# untitled.net
KiCad netlist of a schematic drawn in EAGLE
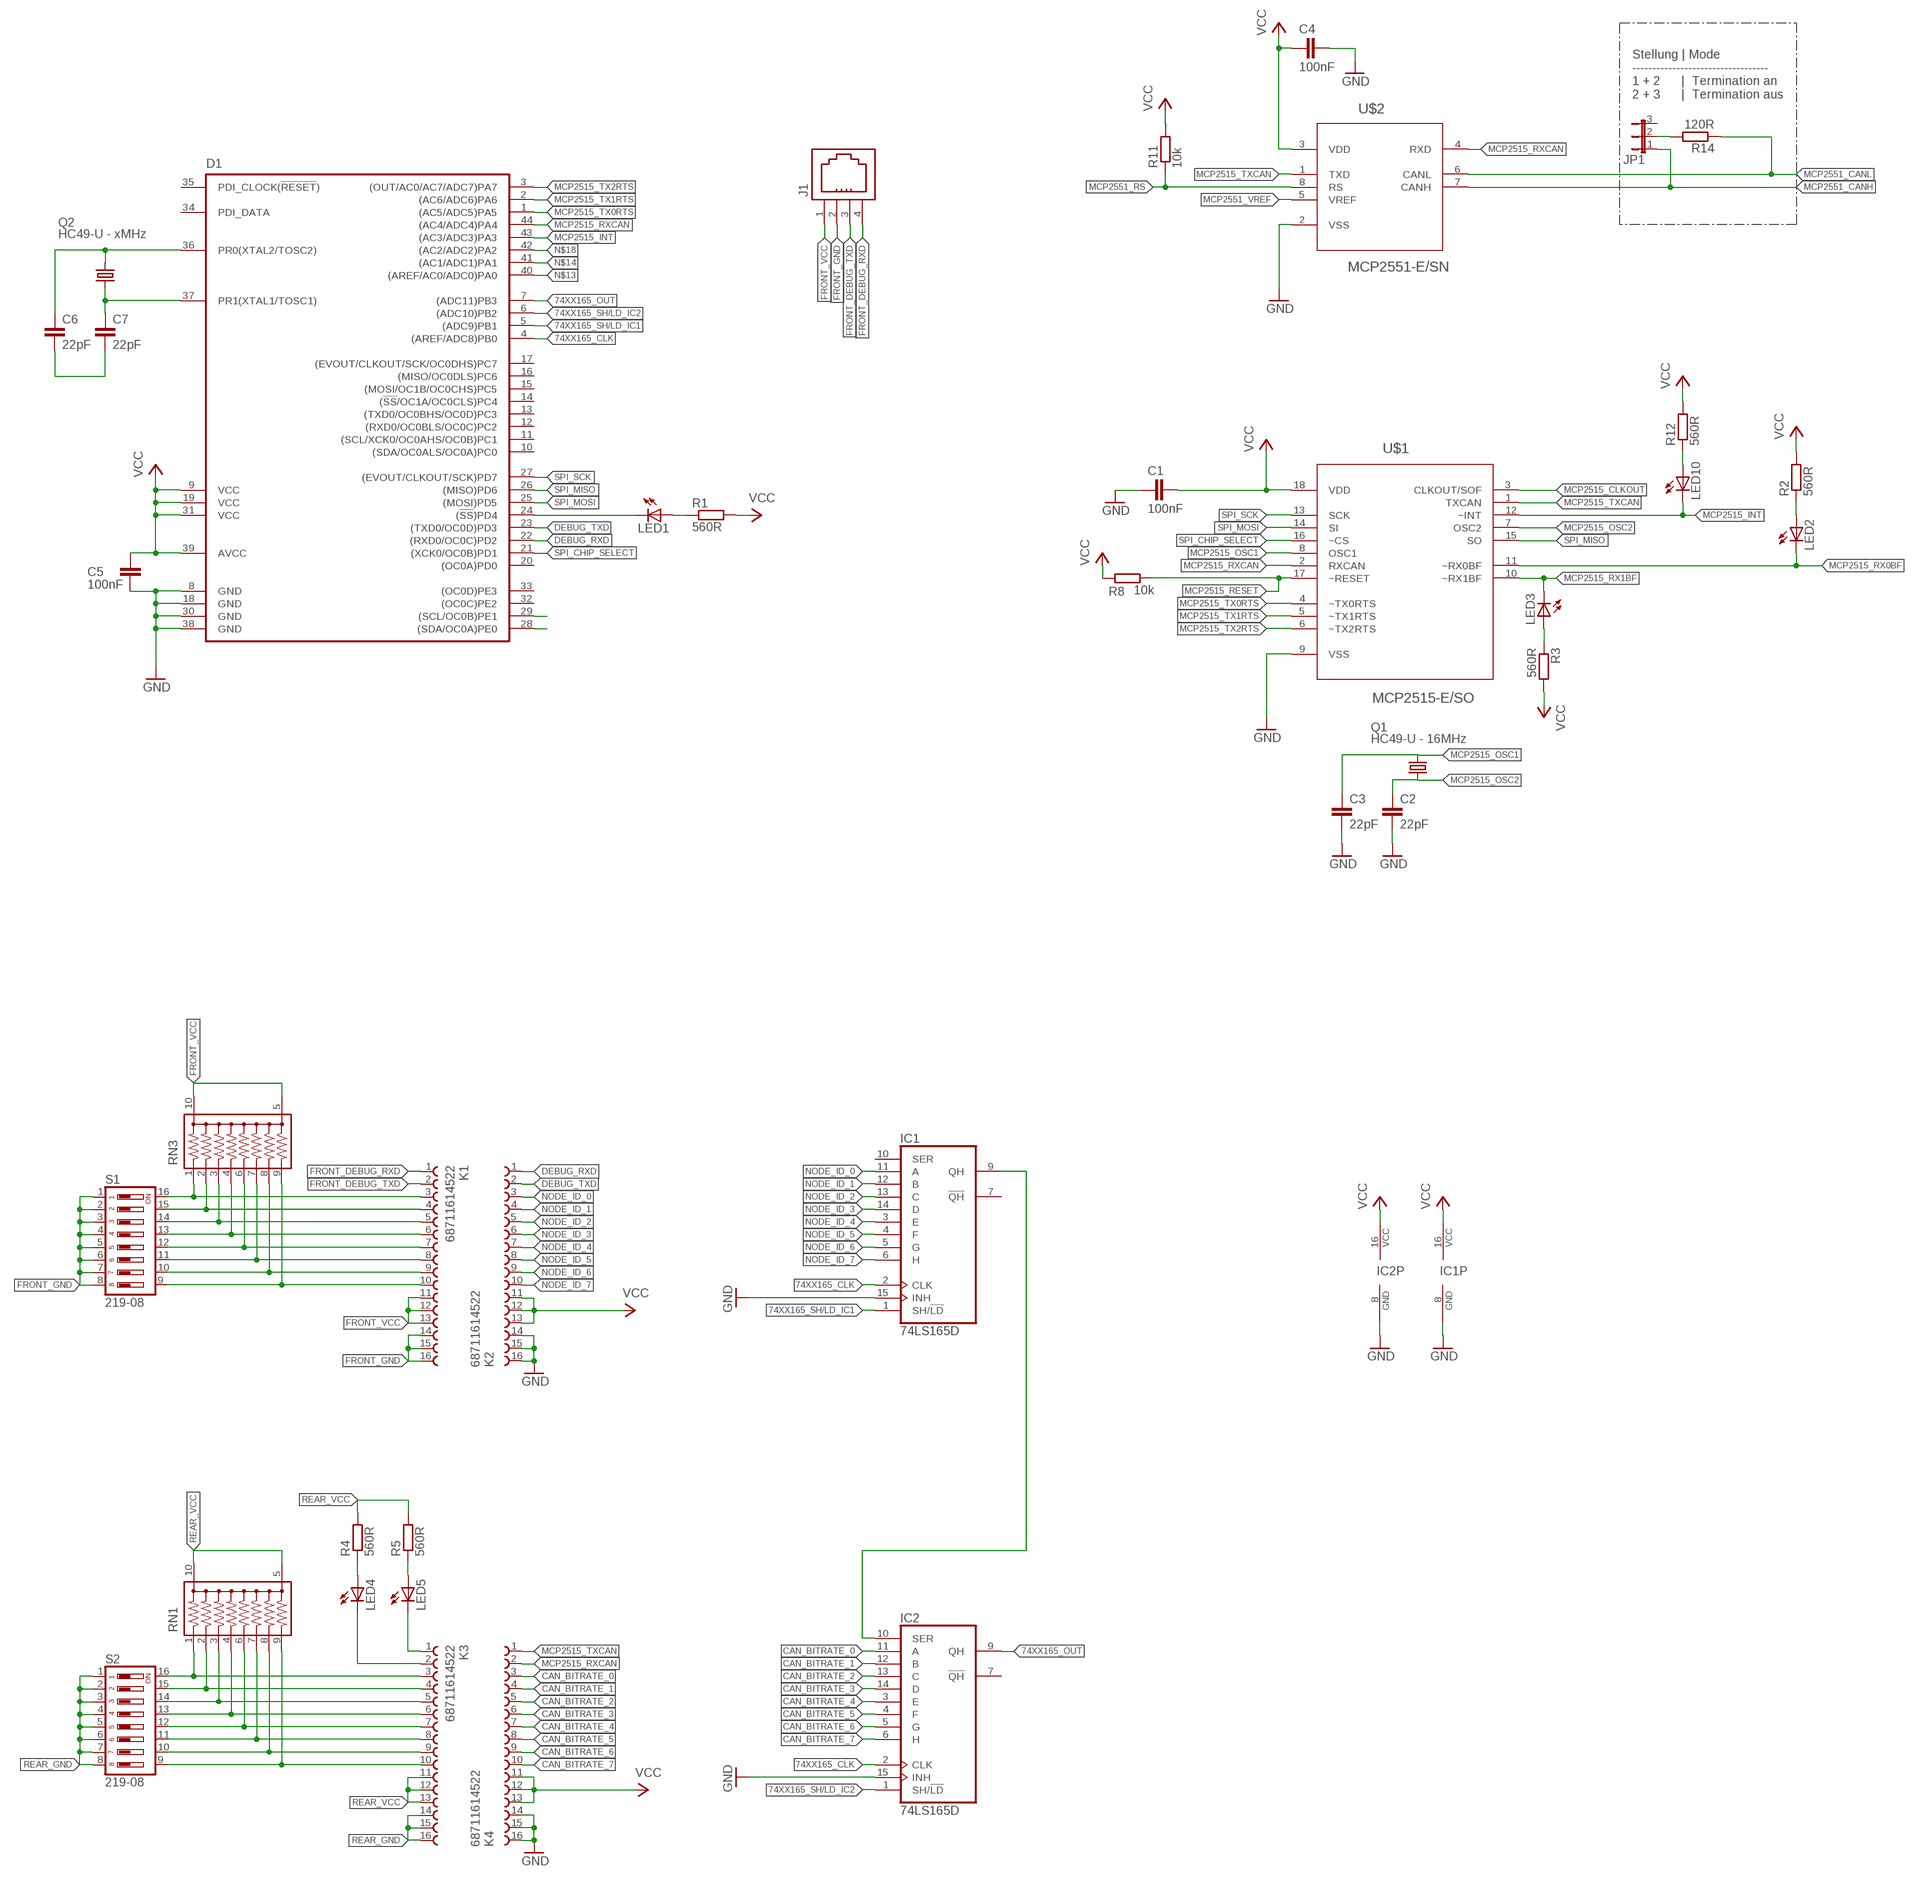
[diagram p0: schematic, sheet 1]

(export (version "E")
  (design (tool "Eeschema 10.0.6"))
  (components
    (comp (ref "C1")
      (value "100nF")
      (footprint "eagle-import:C1206")
      (libsource (lib "eagle-import") (part "C-EUC1206"))
    )
    (comp (ref "C2")
      (value "22pF")
      (footprint "eagle-import:C1206")
      (libsource (lib "eagle-import") (part "C-EUC1206"))
    )
    (comp (ref "C3")
      (value "22pF")
      (footprint "eagle-import:C1206")
      (libsource (lib "eagle-import") (part "C-EUC1206"))
    )
    (comp (ref "C4")
      (value "100nF")
      (footprint "eagle-import:C1206")
      (libsource (lib "eagle-import") (part "C-EUC1206"))
    )
    (comp (ref "C5")
      (value "100nF")
      (footprint "eagle-import:C1206")
      (libsource (lib "eagle-import") (part "C-EUC1206"))
    )
    (comp (ref "C6")
      (value "22pF")
      (footprint "eagle-import:C1206")
      (libsource (lib "eagle-import") (part "C-EUC1206"))
    )
    (comp (ref "C7")
      (value "22pF")
      (footprint "eagle-import:C1206")
      (libsource (lib "eagle-import") (part "C-EUC1206"))
    )
    (comp (ref "D1")
      (value "ATXMEGA16D4/32D4/64D4/128D4-A")
      (footprint "eagle-import:TQFP44A")
      (libsource (lib "eagle-import") (part "ATXMEGA16D4/32D4/64D4/128D4-A"))
    )
    (comp (ref "IC1")
      (value "74LS165D")
      (footprint "eagle-import:SO16")
      (libsource (lib "eagle-import") (part "74165DLS"))
    )
    (comp (ref "IC2")
      (value "74LS165D")
      (footprint "eagle-import:SO16")
      (libsource (lib "eagle-import") (part "74165DLS"))
    )
    (comp (ref "J1")
      (value "615004143821")
      (footprint "eagle-import:615004143821")
      (libsource (lib "eagle-import") (part "615004143821"))
    )
    (comp (ref "JP1")
      (value "JP2E")
      (footprint "eagle-import:JP2")
      (libsource (lib "eagle-import") (part "JP2E"))
    )
    (comp (ref "K1")
      (value "68711614522")
      (footprint "eagle-import:68711614522")
      (libsource (lib "eagle-import") (part "68711614522"))
    )
    (comp (ref "K2")
      (value "68711614522")
      (footprint "eagle-import:68711614522")
      (libsource (lib "eagle-import") (part "68711614522"))
    )
    (comp (ref "K3")
      (value "68711614522")
      (footprint "eagle-import:68711614522")
      (libsource (lib "eagle-import") (part "68711614522"))
    )
    (comp (ref "K4")
      (value "68711614522")
      (footprint "eagle-import:68711614522")
      (libsource (lib "eagle-import") (part "68711614522"))
    )
    (comp (ref "LED1")
      (value "LEDSML1206")
      (footprint "eagle-import:SML1206")
      (libsource (lib "eagle-import") (part "LEDSML1206"))
    )
    (comp (ref "LED2")
      (value "LEDSML1206")
      (footprint "eagle-import:SML1206")
      (libsource (lib "eagle-import") (part "LEDSML1206"))
    )
    (comp (ref "LED3")
      (value "LEDSML1206")
      (footprint "eagle-import:SML1206")
      (libsource (lib "eagle-import") (part "LEDSML1206"))
    )
    (comp (ref "LED4")
      (value "LEDSML1206")
      (footprint "eagle-import:SML1206")
      (libsource (lib "eagle-import") (part "LEDSML1206"))
    )
    (comp (ref "LED5")
      (value "LEDSML1206")
      (footprint "eagle-import:SML1206")
      (libsource (lib "eagle-import") (part "LEDSML1206"))
    )
    (comp (ref "LED10")
      (value "LEDSML1206")
      (footprint "eagle-import:SML1206")
      (libsource (lib "eagle-import") (part "LEDSML1206"))
    )
    (comp (ref "Q1")
      (value "HC49-U - 16MHz")
      (footprint "eagle-import:HC49")
      (libsource (lib "eagle-import") (part "HC49-U"))
    )
    (comp (ref "Q2")
      (value "HC49-U - xMHz")
      (footprint "eagle-import:HC49")
      (libsource (lib "eagle-import") (part "HC49-U"))
    )
    (comp (ref "R1")
      (value "560R")
      (footprint "eagle-import:R1206")
      (libsource (lib "eagle-import") (part "R-EU_R1206"))
    )
    (comp (ref "R2")
      (value "560R")
      (footprint "eagle-import:R1206")
      (libsource (lib "eagle-import") (part "R-EU_R1206"))
    )
    (comp (ref "R3")
      (value "560R")
      (footprint "eagle-import:R1206")
      (libsource (lib "eagle-import") (part "R-EU_R1206"))
    )
    (comp (ref "R4")
      (value "560R")
      (footprint "eagle-import:R1206")
      (libsource (lib "eagle-import") (part "R-EU_R1206"))
    )
    (comp (ref "R5")
      (value "560R")
      (footprint "eagle-import:R1206")
      (libsource (lib "eagle-import") (part "R-EU_R1206"))
    )
    (comp (ref "R8")
      (value "10k")
      (footprint "eagle-import:R1206")
      (libsource (lib "eagle-import") (part "R-EU_R1206"))
    )
    (comp (ref "R11")
      (value "10k")
      (footprint "eagle-import:R1206")
      (libsource (lib "eagle-import") (part "R-EU_R1206"))
    )
    (comp (ref "R12")
      (value "560R")
      (footprint "eagle-import:R1206")
      (libsource (lib "eagle-import") (part "R-EU_R1206"))
    )
    (comp (ref "R14")
      (value "120R")
      (footprint "eagle-import:R1206")
      (libsource (lib "eagle-import") (part "R-EU_R1206"))
    )
    (comp (ref "RN1")
      (value "745-10")
      (footprint "eagle-import:745-10")
      (libsource (lib "eagle-import") (part "745-10"))
    )
    (comp (ref "RN3")
      (value "745-10")
      (footprint "eagle-import:745-10")
      (libsource (lib "eagle-import") (part "745-10"))
    )
    (comp (ref "S1")
      (value "219-08")
      (footprint "eagle-import:CTS-219-08")
      (libsource (lib "eagle-import") (part "219-08"))
    )
    (comp (ref "S2")
      (value "219-08")
      (footprint "eagle-import:CTS-219-08")
      (libsource (lib "eagle-import") (part "219-08"))
    )
    (comp (ref "U$1")
      (value "MCP2515-E/SO")
      (footprint "eagle-import:SOIC127P1030X265-18N")
      (libsource (lib "eagle-import") (part "MCP2515-E/SO"))
    )
    (comp (ref "U$2")
      (value "MCP2551-E/SN")
      (footprint "eagle-import:SOIC127P600X175-8N")
      (libsource (lib "eagle-import") (part "MCP2551-E/SN"))
    )
  )
  (nets
    (net (code "1") (name "74XX165_CLK") (class "Default")
      (node (ref "D1") (pin "4") (pinfunction "(AREF/ADC8)PB0_4") (pintype "bidirectional"))
      (node (ref "IC1") (pin "2") (pinfunction "CLK_2") (pintype "input"))
      (node (ref "IC2") (pin "2") (pinfunction "CLK_2") (pintype "input"))
    )
    (net (code "2") (name "74XX165_OUT") (class "Default")
      (node (ref "D1") (pin "7") (pinfunction "(ADC11)PB3_7") (pintype "bidirectional"))
      (node (ref "IC2") (pin "9") (pinfunction "QH_9") (pintype "output"))
    )
    (net (code "3") (name "74XX165_SH{slash}LD_IC1") (class "Default")
      (node (ref "D1") (pin "5") (pinfunction "(ADC9)PB1_5") (pintype "bidirectional"))
      (node (ref "IC1") (pin "1") (pinfunction "SH/~{LD}_1") (pintype "input"))
    )
    (net (code "4") (name "74XX165_SH{slash}LD_IC2") (class "Default")
      (node (ref "D1") (pin "6") (pinfunction "(ADC10)PB2_6") (pintype "bidirectional"))
      (node (ref "IC2") (pin "1") (pinfunction "SH/~{LD}_1") (pintype "input"))
    )
    (net (code "5") (name "CAN_BITRATE_0") (class "Default")
      (node (ref "IC2") (pin "11") (pinfunction "A_11") (pintype "input"))
      (node (ref "K4") (pin "3") (pinfunction "3_3") (pintype "passive"))
    )
    (net (code "6") (name "CAN_BITRATE_1") (class "Default")
      (node (ref "IC2") (pin "12") (pinfunction "B_12") (pintype "input"))
      (node (ref "K4") (pin "4") (pinfunction "4_4") (pintype "passive"))
    )
    (net (code "7") (name "CAN_BITRATE_2") (class "Default")
      (node (ref "IC2") (pin "13") (pinfunction "C_13") (pintype "input"))
      (node (ref "K4") (pin "5") (pinfunction "5_5") (pintype "passive"))
    )
    (net (code "8") (name "CAN_BITRATE_3") (class "Default")
      (node (ref "IC2") (pin "14") (pinfunction "D_14") (pintype "input"))
      (node (ref "K4") (pin "6") (pinfunction "6_6") (pintype "passive"))
    )
    (net (code "9") (name "CAN_BITRATE_4") (class "Default")
      (node (ref "IC2") (pin "3") (pinfunction "E_3") (pintype "input"))
      (node (ref "K4") (pin "7") (pinfunction "7_7") (pintype "passive"))
    )
    (net (code "10") (name "CAN_BITRATE_5") (class "Default")
      (node (ref "IC2") (pin "4") (pinfunction "F_4") (pintype "input"))
      (node (ref "K4") (pin "8") (pinfunction "8_8") (pintype "passive"))
    )
    (net (code "11") (name "CAN_BITRATE_6") (class "Default")
      (node (ref "IC2") (pin "5") (pinfunction "G_5") (pintype "input"))
      (node (ref "K4") (pin "9") (pinfunction "9_9") (pintype "passive"))
    )
    (net (code "12") (name "CAN_BITRATE_7") (class "Default")
      (node (ref "IC2") (pin "6") (pinfunction "H_6") (pintype "input"))
      (node (ref "K4") (pin "10") (pinfunction "10_10") (pintype "passive"))
    )
    (net (code "13") (name "DEBUG_RXD") (class "Default")
      (node (ref "D1") (pin "22") (pinfunction "(RXD0/OC0C)PD2_22") (pintype "bidirectional"))
      (node (ref "K2") (pin "1") (pinfunction "1_1") (pintype "passive"))
    )
    (net (code "14") (name "DEBUG_TXD") (class "Default")
      (node (ref "D1") (pin "23") (pinfunction "(TXD0/OC0D)PD3_23") (pintype "bidirectional"))
      (node (ref "K2") (pin "2") (pinfunction "2_2") (pintype "passive"))
    )
    (net (code "15") (name "FRONT_DEBUG_RXD") (class "Default")
      (node (ref "J1") (pin "4") (pinfunction "1_4") (pintype "passive"))
      (node (ref "K1") (pin "1") (pinfunction "1_1") (pintype "passive"))
    )
    (net (code "16") (name "FRONT_DEBUG_TXD") (class "Default")
      (node (ref "J1") (pin "3") (pinfunction "2_3") (pintype "passive"))
      (node (ref "K1") (pin "2") (pinfunction "2_2") (pintype "passive"))
    )
    (net (code "17") (name "FRONT_GND") (class "Default")
      (node (ref "J1") (pin "2") (pinfunction "3_2") (pintype "passive"))
      (node (ref "K1") (pin "14") (pinfunction "14_14") (pintype "passive"))
      (node (ref "K1") (pin "15") (pinfunction "15_15") (pintype "passive"))
      (node (ref "K1") (pin "16") (pinfunction "16_16") (pintype "passive"))
      (node (ref "S1") (pin "1") (pinfunction "1_1") (pintype "passive"))
      (node (ref "S1") (pin "2") (pinfunction "2_2") (pintype "passive"))
      (node (ref "S1") (pin "3") (pinfunction "3_3") (pintype "passive"))
      (node (ref "S1") (pin "4") (pinfunction "4_4") (pintype "passive"))
      (node (ref "S1") (pin "5") (pinfunction "5_5") (pintype "passive"))
      (node (ref "S1") (pin "6") (pinfunction "6_6") (pintype "passive"))
      (node (ref "S1") (pin "7") (pinfunction "7_7") (pintype "passive"))
      (node (ref "S1") (pin "8") (pinfunction "8_8") (pintype "passive"))
    )
    (net (code "18") (name "FRONT_VCC") (class "Default")
      (node (ref "J1") (pin "1") (pinfunction "4_1") (pintype "passive"))
      (node (ref "K1") (pin "11") (pinfunction "11_11") (pintype "passive"))
      (node (ref "K1") (pin "12") (pinfunction "12_12") (pintype "passive"))
      (node (ref "K1") (pin "13") (pinfunction "13_13") (pintype "passive"))
      (node (ref "RN3") (pin "10") (pinfunction "10_10") (pintype "passive"))
      (node (ref "RN3") (pin "5") (pinfunction "5_5") (pintype "passive"))
    )
    (net (code "19") (name "GND") (class "Default")
      (node (ref "C1") (pin "2") (pinfunction "2_2") (pintype "passive"))
      (node (ref "C2") (pin "2") (pinfunction "2_2") (pintype "passive"))
      (node (ref "C3") (pin "2") (pinfunction "2_2") (pintype "passive"))
      (node (ref "C4") (pin "1") (pinfunction "1_1") (pintype "passive"))
      (node (ref "C5") (pin "2") (pinfunction "2_2") (pintype "passive"))
      (node (ref "D1") (pin "18") (pinfunction "GND_18") (pintype "power_in"))
      (node (ref "D1") (pin "30") (pinfunction "GND_30") (pintype "power_in"))
      (node (ref "D1") (pin "38") (pinfunction "GND_38") (pintype "power_in"))
      (node (ref "D1") (pin "8") (pinfunction "GND_8") (pintype "power_in"))
      (node (ref "IC1") (pin "15") (pinfunction "INH_15") (pintype "input"))
      (node (ref "IC1") (pin "8") (pinfunction "GND_8") (pintype "power_in"))
      (node (ref "IC2") (pin "15") (pinfunction "INH_15") (pintype "input"))
      (node (ref "IC2") (pin "8") (pinfunction "GND_8") (pintype "power_in"))
      (node (ref "K2") (pin "14") (pinfunction "14_14") (pintype "passive"))
      (node (ref "K2") (pin "15") (pinfunction "15_15") (pintype "passive"))
      (node (ref "K2") (pin "16") (pinfunction "16_16") (pintype "passive"))
      (node (ref "K4") (pin "14") (pinfunction "14_14") (pintype "passive"))
      (node (ref "K4") (pin "15") (pinfunction "15_15") (pintype "passive"))
      (node (ref "K4") (pin "16") (pinfunction "16_16") (pintype "passive"))
      (node (ref "U$1") (pin "9") (pinfunction "VSS_9") (pintype "power_in"))
      (node (ref "U$2") (pin "2") (pinfunction "VSS_2") (pintype "power_in"))
    )
    (net (code "20") (name "MCP2515_CLKOUT") (class "Default")
      (node (ref "U$1") (pin "3") (pinfunction "CLKOUT/SOF_3") (pintype "output"))
    )
    (net (code "21") (name "MCP2515_INT") (class "Default")
      (node (ref "D1") (pin "43") (pinfunction "(AC3/ADC3)PA3_43") (pintype "bidirectional"))
      (node (ref "LED10") (pin "C") (pinfunction "C_C") (pintype "passive"))
      (node (ref "U$1") (pin "12") (pinfunction "~{INT}_12") (pintype "output"))
    )
    (net (code "22") (name "MCP2515_OSC1") (class "Default")
      (node (ref "C3") (pin "1") (pinfunction "1_1") (pintype "passive"))
      (node (ref "Q1") (pin "2") (pinfunction "2_2") (pintype "passive"))
      (node (ref "U$1") (pin "8") (pinfunction "OSC1_8") (pintype "input"))
    )
    (net (code "23") (name "MCP2515_OSC2") (class "Default")
      (node (ref "C2") (pin "1") (pinfunction "1_1") (pintype "passive"))
      (node (ref "Q1") (pin "1") (pinfunction "1_1") (pintype "passive"))
      (node (ref "U$1") (pin "7") (pinfunction "OSC2_7") (pintype "output"))
    )
    (net (code "24") (name "MCP2515_RESET") (class "Default")
      (node (ref "R8") (pin "1") (pinfunction "1_1") (pintype "passive"))
      (node (ref "U$1") (pin "17") (pinfunction "~{RESET}_17") (pintype "input"))
    )
    (net (code "25") (name "MCP2515_RX0BF") (class "Default")
      (node (ref "LED2") (pin "C") (pinfunction "C_C") (pintype "passive"))
      (node (ref "U$1") (pin "11") (pinfunction "~{RX0BF}_11") (pintype "output"))
    )
    (net (code "26") (name "MCP2515_RX1BF") (class "Default")
      (node (ref "LED3") (pin "C") (pinfunction "C_C") (pintype "passive"))
      (node (ref "U$1") (pin "10") (pinfunction "~{RX1BF}_10") (pintype "output"))
    )
    (net (code "27") (name "MCP2515_RXCAN") (class "Default")
      (node (ref "D1") (pin "44") (pinfunction "(AC4/ADC4)PA4_44") (pintype "bidirectional"))
      (node (ref "K4") (pin "2") (pinfunction "2_2") (pintype "passive"))
      (node (ref "U$1") (pin "2") (pinfunction "RXCAN_2") (pintype "input"))
      (node (ref "U$2") (pin "4") (pinfunction "RXD_4") (pintype "output"))
    )
    (net (code "28") (name "MCP2515_TX0RTS") (class "Default")
      (node (ref "D1") (pin "1") (pinfunction "(AC5/ADC5)PA5_1") (pintype "bidirectional"))
      (node (ref "U$1") (pin "4") (pinfunction "~{TX0RTS}_4") (pintype "input"))
    )
    (net (code "29") (name "MCP2515_TX1RTS") (class "Default")
      (node (ref "D1") (pin "2") (pinfunction "(AC6/ADC6)PA6_2") (pintype "bidirectional"))
      (node (ref "U$1") (pin "5") (pinfunction "~{TX1RTS}_5") (pintype "input"))
    )
    (net (code "30") (name "MCP2515_TX2RTS") (class "Default")
      (node (ref "D1") (pin "3") (pinfunction "(OUT/AC0/AC7/ADC7)PA7_3") (pintype "bidirectional"))
      (node (ref "U$1") (pin "6") (pinfunction "~{TX2RTS}_6") (pintype "input"))
    )
    (net (code "31") (name "MCP2515_TXCAN") (class "Default")
      (node (ref "K4") (pin "1") (pinfunction "1_1") (pintype "passive"))
      (node (ref "U$1") (pin "1") (pinfunction "TXCAN_1") (pintype "output"))
      (node (ref "U$2") (pin "1") (pinfunction "TXD_1") (pintype "input"))
    )
    (net (code "32") (name "MCP2551_CANH") (class "Default")
      (node (ref "JP1") (pin "1") (pinfunction "1_1") (pintype "passive"))
      (node (ref "U$2") (pin "7") (pinfunction "CANH_7") (pintype "output"))
    )
    (net (code "33") (name "MCP2551_CANL") (class "Default")
      (node (ref "R14") (pin "1") (pinfunction "1_1") (pintype "passive"))
      (node (ref "U$2") (pin "6") (pinfunction "CANL_6") (pintype "output"))
    )
    (net (code "34") (name "MCP2551_RS") (class "Default")
      (node (ref "R11") (pin "1") (pinfunction "1_1") (pintype "passive"))
      (node (ref "U$2") (pin "8") (pinfunction "RS_8") (pintype "input"))
    )
    (net (code "35") (name "MCP2551_VREF") (class "Default")
      (node (ref "U$2") (pin "5") (pinfunction "VREF_5") (pintype "input"))
    )
    (net (code "36") (name "N$13") (class "Default")
      (node (ref "D1") (pin "40") (pinfunction "(AREF/AC0/ADC0)PA0_40") (pintype "bidirectional"))
    )
    (net (code "37") (name "N$14") (class "Default")
      (node (ref "D1") (pin "41") (pinfunction "(AC1/ADC1)PA1_41") (pintype "bidirectional"))
    )
    (net (code "38") (name "N$18") (class "Default")
      (node (ref "D1") (pin "42") (pinfunction "(AC2/ADC2)PA2_42") (pintype "bidirectional"))
    )
    (net (code "39") (name "NODE_ID_0") (class "Default")
      (node (ref "IC1") (pin "11") (pinfunction "A_11") (pintype "input"))
      (node (ref "K2") (pin "3") (pinfunction "3_3") (pintype "passive"))
    )
    (net (code "40") (name "NODE_ID_1") (class "Default")
      (node (ref "IC1") (pin "12") (pinfunction "B_12") (pintype "input"))
      (node (ref "K2") (pin "4") (pinfunction "4_4") (pintype "passive"))
    )
    (net (code "41") (name "NODE_ID_2") (class "Default")
      (node (ref "IC1") (pin "13") (pinfunction "C_13") (pintype "input"))
      (node (ref "K2") (pin "5") (pinfunction "5_5") (pintype "passive"))
    )
    (net (code "42") (name "NODE_ID_3") (class "Default")
      (node (ref "IC1") (pin "14") (pinfunction "D_14") (pintype "input"))
      (node (ref "K2") (pin "6") (pinfunction "6_6") (pintype "passive"))
    )
    (net (code "43") (name "NODE_ID_4") (class "Default")
      (node (ref "IC1") (pin "3") (pinfunction "E_3") (pintype "input"))
      (node (ref "K2") (pin "7") (pinfunction "7_7") (pintype "passive"))
    )
    (net (code "44") (name "NODE_ID_5") (class "Default")
      (node (ref "IC1") (pin "4") (pinfunction "F_4") (pintype "input"))
      (node (ref "K2") (pin "8") (pinfunction "8_8") (pintype "passive"))
    )
    (net (code "45") (name "NODE_ID_6") (class "Default")
      (node (ref "IC1") (pin "5") (pinfunction "G_5") (pintype "input"))
      (node (ref "K2") (pin "9") (pinfunction "9_9") (pintype "passive"))
    )
    (net (code "46") (name "NODE_ID_7") (class "Default")
      (node (ref "IC1") (pin "6") (pinfunction "H_6") (pintype "input"))
      (node (ref "K2") (pin "10") (pinfunction "10_10") (pintype "passive"))
    )
    (net (code "47") (name "Net-(C6-Pad2)") (class "Default")
      (node (ref "C6") (pin "2") (pinfunction "2_2") (pintype "passive"))
      (node (ref "C7") (pin "2") (pinfunction "2_2") (pintype "passive"))
    )
    (net (code "48") (name "Net-(D1-(~{SS})PD4)") (class "Default")
      (node (ref "D1") (pin "24") (pinfunction "(~{SS})PD4_24") (pintype "bidirectional"))
      (node (ref "LED1") (pin "C") (pinfunction "C_C") (pintype "passive"))
    )
    (net (code "49") (name "Net-(D1-PR0(XTAL2{slash}TOSC2))") (class "Default")
      (node (ref "C6") (pin "1") (pinfunction "1_1") (pintype "passive"))
      (node (ref "D1") (pin "36") (pinfunction "PR0(XTAL2/TOSC2)_36") (pintype "bidirectional"))
      (node (ref "Q2") (pin "2") (pinfunction "2_2") (pintype "passive"))
    )
    (net (code "50") (name "Net-(D1-PR1(XTAL1{slash}TOSC1))") (class "Default")
      (node (ref "C7") (pin "1") (pinfunction "1_1") (pintype "passive"))
      (node (ref "D1") (pin "37") (pinfunction "PR1(XTAL1/TOSC1)_37") (pintype "bidirectional"))
      (node (ref "Q2") (pin "1") (pinfunction "1_1") (pintype "passive"))
    )
    (net (code "51") (name "Net-(IC1A-QH)") (class "Default")
      (node (ref "IC1") (pin "9") (pinfunction "QH_9") (pintype "output"))
      (node (ref "IC2") (pin "10") (pinfunction "SER_10") (pintype "input"))
    )
    (net (code "52") (name "Net-(JP1-Pad2)") (class "Default")
      (node (ref "JP1") (pin "2") (pinfunction "2_2") (pintype "passive"))
      (node (ref "R14") (pin "2") (pinfunction "2_2") (pintype "passive"))
    )
    (net (code "53") (name "Net-(K1-Pad3)") (class "Default")
      (node (ref "K1") (pin "3") (pinfunction "3_3") (pintype "passive"))
      (node (ref "RN3") (pin "1") (pinfunction "1_1") (pintype "passive"))
      (node (ref "S1") (pin "16") (pinfunction "16_16") (pintype "passive"))
    )
    (net (code "54") (name "Net-(K1-Pad4)") (class "Default")
      (node (ref "K1") (pin "4") (pinfunction "4_4") (pintype "passive"))
      (node (ref "RN3") (pin "2") (pinfunction "2_2") (pintype "passive"))
      (node (ref "S1") (pin "15") (pinfunction "15_15") (pintype "passive"))
    )
    (net (code "55") (name "Net-(K1-Pad5)") (class "Default")
      (node (ref "K1") (pin "5") (pinfunction "5_5") (pintype "passive"))
      (node (ref "RN3") (pin "3") (pinfunction "3_3") (pintype "passive"))
      (node (ref "S1") (pin "14") (pinfunction "14_14") (pintype "passive"))
    )
    (net (code "56") (name "Net-(K1-Pad6)") (class "Default")
      (node (ref "K1") (pin "6") (pinfunction "6_6") (pintype "passive"))
      (node (ref "RN3") (pin "4") (pinfunction "4_4") (pintype "passive"))
      (node (ref "S1") (pin "13") (pinfunction "13_13") (pintype "passive"))
    )
    (net (code "57") (name "Net-(K1-Pad7)") (class "Default")
      (node (ref "K1") (pin "7") (pinfunction "7_7") (pintype "passive"))
      (node (ref "RN3") (pin "6") (pinfunction "6_6") (pintype "passive"))
      (node (ref "S1") (pin "12") (pinfunction "12_12") (pintype "passive"))
    )
    (net (code "58") (name "Net-(K1-Pad8)") (class "Default")
      (node (ref "K1") (pin "8") (pinfunction "8_8") (pintype "passive"))
      (node (ref "RN3") (pin "7") (pinfunction "7_7") (pintype "passive"))
      (node (ref "S1") (pin "11") (pinfunction "11_11") (pintype "passive"))
    )
    (net (code "59") (name "Net-(K1-Pad9)") (class "Default")
      (node (ref "K1") (pin "9") (pinfunction "9_9") (pintype "passive"))
      (node (ref "RN3") (pin "8") (pinfunction "8_8") (pintype "passive"))
      (node (ref "S1") (pin "10") (pinfunction "10_10") (pintype "passive"))
    )
    (net (code "60") (name "Net-(K1-Pad10)") (class "Default")
      (node (ref "K1") (pin "10") (pinfunction "10_10") (pintype "passive"))
      (node (ref "RN3") (pin "9") (pinfunction "9_9") (pintype "passive"))
      (node (ref "S1") (pin "9") (pinfunction "9_9") (pintype "passive"))
    )
    (net (code "61") (name "Net-(K3-Pad1)") (class "Default")
      (node (ref "K3") (pin "1") (pinfunction "1_1") (pintype "passive"))
      (node (ref "LED5") (pin "C") (pinfunction "C_C") (pintype "passive"))
    )
    (net (code "62") (name "Net-(K3-Pad2)") (class "Default")
      (node (ref "K3") (pin "2") (pinfunction "2_2") (pintype "passive"))
      (node (ref "LED4") (pin "C") (pinfunction "C_C") (pintype "passive"))
    )
    (net (code "63") (name "Net-(K3-Pad3)") (class "Default")
      (node (ref "K3") (pin "3") (pinfunction "3_3") (pintype "passive"))
      (node (ref "RN1") (pin "1") (pinfunction "1_1") (pintype "passive"))
      (node (ref "S2") (pin "16") (pinfunction "16_16") (pintype "passive"))
    )
    (net (code "64") (name "Net-(K3-Pad4)") (class "Default")
      (node (ref "K3") (pin "4") (pinfunction "4_4") (pintype "passive"))
      (node (ref "RN1") (pin "2") (pinfunction "2_2") (pintype "passive"))
      (node (ref "S2") (pin "15") (pinfunction "15_15") (pintype "passive"))
    )
    (net (code "65") (name "Net-(K3-Pad5)") (class "Default")
      (node (ref "K3") (pin "5") (pinfunction "5_5") (pintype "passive"))
      (node (ref "RN1") (pin "3") (pinfunction "3_3") (pintype "passive"))
      (node (ref "S2") (pin "14") (pinfunction "14_14") (pintype "passive"))
    )
    (net (code "66") (name "Net-(K3-Pad6)") (class "Default")
      (node (ref "K3") (pin "6") (pinfunction "6_6") (pintype "passive"))
      (node (ref "RN1") (pin "4") (pinfunction "4_4") (pintype "passive"))
      (node (ref "S2") (pin "13") (pinfunction "13_13") (pintype "passive"))
    )
    (net (code "67") (name "Net-(K3-Pad7)") (class "Default")
      (node (ref "K3") (pin "7") (pinfunction "7_7") (pintype "passive"))
      (node (ref "RN1") (pin "6") (pinfunction "6_6") (pintype "passive"))
      (node (ref "S2") (pin "12") (pinfunction "12_12") (pintype "passive"))
    )
    (net (code "68") (name "Net-(K3-Pad8)") (class "Default")
      (node (ref "K3") (pin "8") (pinfunction "8_8") (pintype "passive"))
      (node (ref "RN1") (pin "7") (pinfunction "7_7") (pintype "passive"))
      (node (ref "S2") (pin "11") (pinfunction "11_11") (pintype "passive"))
    )
    (net (code "69") (name "Net-(K3-Pad9)") (class "Default")
      (node (ref "K3") (pin "9") (pinfunction "9_9") (pintype "passive"))
      (node (ref "RN1") (pin "8") (pinfunction "8_8") (pintype "passive"))
      (node (ref "S2") (pin "10") (pinfunction "10_10") (pintype "passive"))
    )
    (net (code "70") (name "Net-(K3-Pad10)") (class "Default")
      (node (ref "K3") (pin "10") (pinfunction "10_10") (pintype "passive"))
      (node (ref "RN1") (pin "9") (pinfunction "9_9") (pintype "passive"))
      (node (ref "S2") (pin "9") (pinfunction "9_9") (pintype "passive"))
    )
    (net (code "71") (name "Net-(LED1-PadA)") (class "Default")
      (node (ref "LED1") (pin "A") (pinfunction "A_A") (pintype "passive"))
      (node (ref "R1") (pin "1") (pinfunction "1_1") (pintype "passive"))
    )
    (net (code "72") (name "Net-(LED2-PadA)") (class "Default")
      (node (ref "LED2") (pin "A") (pinfunction "A_A") (pintype "passive"))
      (node (ref "R2") (pin "1") (pinfunction "1_1") (pintype "passive"))
    )
    (net (code "73") (name "Net-(LED3-PadA)") (class "Default")
      (node (ref "LED3") (pin "A") (pinfunction "A_A") (pintype "passive"))
      (node (ref "R3") (pin "1") (pinfunction "1_1") (pintype "passive"))
    )
    (net (code "74") (name "Net-(LED4-PadA)") (class "Default")
      (node (ref "LED4") (pin "A") (pinfunction "A_A") (pintype "passive"))
      (node (ref "R4") (pin "1") (pinfunction "1_1") (pintype "passive"))
    )
    (net (code "75") (name "Net-(LED5-PadA)") (class "Default")
      (node (ref "LED5") (pin "A") (pinfunction "A_A") (pintype "passive"))
      (node (ref "R5") (pin "1") (pinfunction "1_1") (pintype "passive"))
    )
    (net (code "76") (name "Net-(LED10-PadA)") (class "Default")
      (node (ref "LED10") (pin "A") (pinfunction "A_A") (pintype "passive"))
      (node (ref "R12") (pin "1") (pinfunction "1_1") (pintype "passive"))
    )
    (net (code "77") (name "REAR_GND") (class "Default")
      (node (ref "K3") (pin "14") (pinfunction "14_14") (pintype "passive"))
      (node (ref "K3") (pin "15") (pinfunction "15_15") (pintype "passive"))
      (node (ref "K3") (pin "16") (pinfunction "16_16") (pintype "passive"))
      (node (ref "S2") (pin "1") (pinfunction "1_1") (pintype "passive"))
      (node (ref "S2") (pin "2") (pinfunction "2_2") (pintype "passive"))
      (node (ref "S2") (pin "3") (pinfunction "3_3") (pintype "passive"))
      (node (ref "S2") (pin "4") (pinfunction "4_4") (pintype "passive"))
      (node (ref "S2") (pin "5") (pinfunction "5_5") (pintype "passive"))
      (node (ref "S2") (pin "6") (pinfunction "6_6") (pintype "passive"))
      (node (ref "S2") (pin "7") (pinfunction "7_7") (pintype "passive"))
      (node (ref "S2") (pin "8") (pinfunction "8_8") (pintype "passive"))
    )
    (net (code "78") (name "REAR_VCC") (class "Default")
      (node (ref "K3") (pin "11") (pinfunction "11_11") (pintype "passive"))
      (node (ref "K3") (pin "12") (pinfunction "12_12") (pintype "passive"))
      (node (ref "K3") (pin "13") (pinfunction "13_13") (pintype "passive"))
      (node (ref "R4") (pin "2") (pinfunction "2_2") (pintype "passive"))
      (node (ref "R5") (pin "2") (pinfunction "2_2") (pintype "passive"))
      (node (ref "RN1") (pin "10") (pinfunction "10_10") (pintype "passive"))
      (node (ref "RN1") (pin "5") (pinfunction "5_5") (pintype "passive"))
    )
    (net (code "79") (name "SPI_CHIP_SELECT") (class "Default")
      (node (ref "D1") (pin "21") (pinfunction "(XCK0/OC0B)PD1_21") (pintype "bidirectional"))
      (node (ref "U$1") (pin "16") (pinfunction "~{CS}_16") (pintype "input"))
    )
    (net (code "80") (name "SPI_MISO") (class "Default")
      (node (ref "D1") (pin "26") (pinfunction "(MISO)PD6_26") (pintype "bidirectional"))
      (node (ref "U$1") (pin "15") (pinfunction "SO_15") (pintype "output"))
    )
    (net (code "81") (name "SPI_MOSI") (class "Default")
      (node (ref "D1") (pin "25") (pinfunction "(MOSI)PD5_25") (pintype "bidirectional"))
      (node (ref "U$1") (pin "14") (pinfunction "SI_14") (pintype "input"))
    )
    (net (code "82") (name "SPI_SCK") (class "Default")
      (node (ref "D1") (pin "27") (pinfunction "(EVOUT/CLKOUT/SCK)PD7_27") (pintype "bidirectional"))
      (node (ref "U$1") (pin "13") (pinfunction "SCK_13") (pintype "input"))
    )
    (net (code "83") (name "VCC") (class "Default")
      (node (ref "C1") (pin "1") (pinfunction "1_1") (pintype "passive"))
      (node (ref "C4") (pin "2") (pinfunction "2_2") (pintype "passive"))
      (node (ref "C5") (pin "1") (pinfunction "1_1") (pintype "passive"))
      (node (ref "D1") (pin "19") (pinfunction "VCC_19") (pintype "power_in"))
      (node (ref "D1") (pin "31") (pinfunction "VCC_31") (pintype "power_in"))
      (node (ref "D1") (pin "39") (pinfunction "AVCC_39") (pintype "power_in"))
      (node (ref "D1") (pin "9") (pinfunction "VCC_9") (pintype "power_in"))
      (node (ref "IC1") (pin "16") (pinfunction "VCC_16") (pintype "power_in"))
      (node (ref "IC2") (pin "16") (pinfunction "VCC_16") (pintype "power_in"))
      (node (ref "K2") (pin "11") (pinfunction "11_11") (pintype "passive"))
      (node (ref "K2") (pin "12") (pinfunction "12_12") (pintype "passive"))
      (node (ref "K2") (pin "13") (pinfunction "13_13") (pintype "passive"))
      (node (ref "K4") (pin "11") (pinfunction "11_11") (pintype "passive"))
      (node (ref "K4") (pin "12") (pinfunction "12_12") (pintype "passive"))
      (node (ref "K4") (pin "13") (pinfunction "13_13") (pintype "passive"))
      (node (ref "R1") (pin "2") (pinfunction "2_2") (pintype "passive"))
      (node (ref "R11") (pin "2") (pinfunction "2_2") (pintype "passive"))
      (node (ref "R12") (pin "2") (pinfunction "2_2") (pintype "passive"))
      (node (ref "R2") (pin "2") (pinfunction "2_2") (pintype "passive"))
      (node (ref "R3") (pin "2") (pinfunction "2_2") (pintype "passive"))
      (node (ref "R8") (pin "2") (pinfunction "2_2") (pintype "passive"))
      (node (ref "U$1") (pin "18") (pinfunction "VDD_18") (pintype "power_in"))
      (node (ref "U$2") (pin "3") (pinfunction "VDD_3") (pintype "power_in"))
    )
    (net (code "84") (name "unconnected-(D1-(EVOUT{slash}CLKOUT{slash}SCK{slash}OC0DHS)PC7-Pad17)") (class "Default")
      (node (ref "D1") (pin "17") (pinfunction "(EVOUT/CLKOUT/SCK/OC0DHS)PC7_17") (pintype "bidirectional"))
    )
    (net (code "85") (name "unconnected-(D1-(MISO{slash}OC0DLS)PC6-Pad16)") (class "Default")
      (node (ref "D1") (pin "16") (pinfunction "(MISO/OC0DLS)PC6_16") (pintype "bidirectional"))
    )
    (net (code "86") (name "unconnected-(D1-(MOSI{slash}OC1B{slash}OC0CHS)PC5-Pad15)") (class "Default")
      (node (ref "D1") (pin "15") (pinfunction "(MOSI/OC1B/OC0CHS)PC5_15") (pintype "bidirectional"))
    )
    (net (code "87") (name "unconnected-(D1-(OC0A)PD0-Pad20)") (class "Default")
      (node (ref "D1") (pin "20") (pinfunction "(OC0A)PD0_20") (pintype "bidirectional"))
    )
    (net (code "88") (name "unconnected-(D1-(OC0C)PE2-Pad32)") (class "Default")
      (node (ref "D1") (pin "32") (pinfunction "(OC0C)PE2_32") (pintype "bidirectional"))
    )
    (net (code "89") (name "unconnected-(D1-(OC0D)PE3-Pad33)") (class "Default")
      (node (ref "D1") (pin "33") (pinfunction "(OC0D)PE3_33") (pintype "bidirectional"))
    )
    (net (code "90") (name "unconnected-(D1-(RXD0{slash}OC0BLS{slash}OC0C)PC2-Pad12)") (class "Default")
      (node (ref "D1") (pin "12") (pinfunction "(RXD0/OC0BLS/OC0C)PC2_12") (pintype "bidirectional"))
    )
    (net (code "91") (name "unconnected-(D1-(SCL{slash}OC0B)PE1-Pad29)") (class "Default")
      (node (ref "D1") (pin "29") (pinfunction "(SCL/OC0B)PE1_29") (pintype "bidirectional"))
    )
    (net (code "92") (name "unconnected-(D1-(SCL{slash}XCK0{slash}OC0AHS{slash}OC0B)PC1-Pad11)") (class "Default")
      (node (ref "D1") (pin "11") (pinfunction "(SCL/XCK0/OC0AHS/OC0B)PC1_11") (pintype "bidirectional"))
    )
    (net (code "93") (name "unconnected-(D1-(SDA{slash}OC0A)PE0-Pad28)") (class "Default")
      (node (ref "D1") (pin "28") (pinfunction "(SDA/OC0A)PE0_28") (pintype "bidirectional"))
    )
    (net (code "94") (name "unconnected-(D1-(SDA{slash}OC0ALS{slash}OC0A)PC0-Pad10)") (class "Default")
      (node (ref "D1") (pin "10") (pinfunction "(SDA/OC0ALS/OC0A)PC0_10") (pintype "bidirectional"))
    )
    (net (code "95") (name "unconnected-(D1-(TXD0{slash}OC0BHS{slash}OC0D)PC3-Pad13)") (class "Default")
      (node (ref "D1") (pin "13") (pinfunction "(TXD0/OC0BHS/OC0D)PC3_13") (pintype "bidirectional"))
    )
    (net (code "96") (name "unconnected-(D1-(~{SS}{slash}OC1A{slash}OC0CLS)PC4-Pad14)") (class "Default")
      (node (ref "D1") (pin "14") (pinfunction "(~{SS}/OC1A/OC0CLS)PC4_14") (pintype "bidirectional"))
    )
    (net (code "97") (name "unconnected-(D1-PDI_CLOCK(~{RESET})-Pad35)") (class "Default")
      (node (ref "D1") (pin "35") (pinfunction "PDI_CLOCK(~{RESET})_35") (pintype "input"))
    )
    (net (code "98") (name "unconnected-(D1-PDI_DATA-Pad34)") (class "Default")
      (node (ref "D1") (pin "34") (pinfunction "PDI_DATA_34") (pintype "bidirectional"))
    )
    (net (code "99") (name "unconnected-(IC1A-SER-Pad10)") (class "Default")
      (node (ref "IC1") (pin "10") (pinfunction "SER_10") (pintype "input"))
    )
    (net (code "100") (name "unconnected-(IC1A-~{QH}-Pad7)") (class "Default")
      (node (ref "IC1") (pin "7") (pinfunction "~{QH}_7") (pintype "output"))
    )
    (net (code "101") (name "unconnected-(IC2A-~{QH}-Pad7)") (class "Default")
      (node (ref "IC2") (pin "7") (pinfunction "~{QH}_7") (pintype "output"))
    )
    (net (code "102") (name "unconnected-(JP1-Pad3)") (class "Default")
      (node (ref "JP1") (pin "3") (pinfunction "3_3") (pintype "passive"))
    )
  )
)
